# 8266_ultrasonic.net
KiCad netlist of a schematic drawn in EAGLE
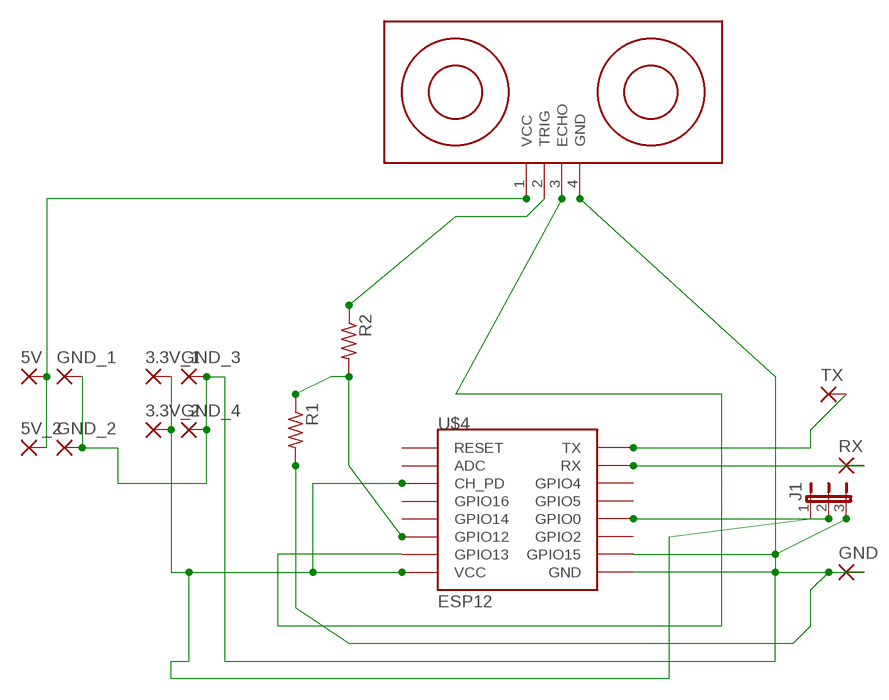
[diagram p0: schematic, sheet 1]

(export (version "E")
  (design (tool "Eeschema 10.0.6"))
  (components
    (comp (ref "3.3V_1")
      (value "2,15/1,0")
      (footprint "eagle-import:2,15_1,0")
      (libsource (lib "eagle-import") (part "2,15/1,0"))
    )
    (comp (ref "3.3V_2")
      (value "2,15/1,0")
      (footprint "eagle-import:2,15_1,0")
      (libsource (lib "eagle-import") (part "2,15/1,0"))
    )
    (comp (ref "5V")
      (value "2,15/1,0")
      (footprint "eagle-import:2,15_1,0")
      (libsource (lib "eagle-import") (part "2,15/1,0"))
    )
    (comp (ref "5V_2")
      (value "2,15/1,0")
      (footprint "eagle-import:2,15_1,0")
      (libsource (lib "eagle-import") (part "2,15/1,0"))
    )
    (comp (ref "GND")
      (value "2,15/1,0")
      (footprint "eagle-import:2,15_1,0")
      (libsource (lib "eagle-import") (part "2,15/1,0"))
    )
    (comp (ref "GND_1")
      (value "2,15/1,0")
      (footprint "eagle-import:2,15_1,0")
      (libsource (lib "eagle-import") (part "2,15/1,0"))
    )
    (comp (ref "GND_2")
      (value "2,15/1,0")
      (footprint "eagle-import:2,15_1,0")
      (libsource (lib "eagle-import") (part "2,15/1,0"))
    )
    (comp (ref "GND_3")
      (value "2,15/1,0")
      (footprint "eagle-import:2,15_1,0")
      (libsource (lib "eagle-import") (part "2,15/1,0"))
    )
    (comp (ref "GND_4")
      (value "2,15/1,0")
      (footprint "eagle-import:2,15_1,0")
      (libsource (lib "eagle-import") (part "2,15/1,0"))
    )
    (comp (ref "J1")
      (value "JP2E")
      (footprint "eagle-import:JP2")
      (libsource (lib "eagle-import") (part "JP2E"))
    )
    (comp (ref "R1")
      (value "R-US_0207/10")
      (footprint "eagle-import:0207_10")
      (libsource (lib "eagle-import") (part "R-US_0207/10"))
    )
    (comp (ref "R2")
      (value "R-US_0207/10")
      (footprint "eagle-import:0207_10")
      (libsource (lib "eagle-import") (part "R-US_0207/10"))
    )
    (comp (ref "RX")
      (value "2,15/1,0")
      (footprint "eagle-import:2,15_1,0")
      (libsource (lib "eagle-import") (part "2,15/1,0"))
    )
    (comp (ref "TX")
      (value "2,15/1,0")
      (footprint "eagle-import:2,15_1,0")
      (libsource (lib "eagle-import") (part "2,15/1,0"))
    )
    (comp (ref "U$3")
      (value "ULTRASONIC-HC-SR04#V")
      (footprint "eagle-import:ULTRASONIC-HC-SR04#V")
      (libsource (lib "eagle-import") (part "ULTRASONIC-HC-SR04#V"))
    )
    (comp (ref "U$4")
      (value "ESP12")
      (footprint "eagle-import:ESP12")
      (libsource (lib "eagle-import") (part "ESP12"))
    )
  )
  (nets
    (net (code "1") (name "Net-(3.3V_1-P)") (class "Default")
      (node (ref "3.3V_1") (pin "1") (pinfunction "P_1") (pintype "passive"))
      (node (ref "3.3V_2") (pin "1") (pinfunction "P_1") (pintype "passive"))
      (node (ref "J1") (pin "1") (pinfunction "1_1") (pintype "passive"))
      (node (ref "U$4") (pin "CH_PD") (pinfunction "CH_PD_CH_PD") (pintype "bidirectional"))
      (node (ref "U$4") (pin "VCC") (pinfunction "VCC_VCC") (pintype "bidirectional"))
    )
    (net (code "2") (name "Net-(5V-P)") (class "Default")
      (node (ref "5V") (pin "1") (pinfunction "P_1") (pintype "passive"))
      (node (ref "5V_2") (pin "1") (pinfunction "P_1") (pintype "passive"))
      (node (ref "U$3") (pin "1") (pinfunction "VCC_1") (pintype "power_in"))
    )
    (net (code "3") (name "Net-(GND-P)") (class "Default")
      (node (ref "GND") (pin "1") (pinfunction "P_1") (pintype "passive"))
      (node (ref "GND_1") (pin "1") (pinfunction "P_1") (pintype "passive"))
      (node (ref "GND_2") (pin "1") (pinfunction "P_1") (pintype "passive"))
      (node (ref "GND_3") (pin "1") (pinfunction "P_1") (pintype "passive"))
      (node (ref "GND_4") (pin "1") (pinfunction "P_1") (pintype "passive"))
      (node (ref "J1") (pin "3") (pinfunction "3_3") (pintype "passive"))
      (node (ref "R1") (pin "2") (pinfunction "2_2") (pintype "passive"))
      (node (ref "U$3") (pin "4") (pinfunction "GND_4") (pintype "power_in"))
      (node (ref "U$4") (pin "GND") (pinfunction "GND_GND") (pintype "bidirectional"))
      (node (ref "U$4") (pin "GPIO15") (pinfunction "GPIO15_GPIO15") (pintype "bidirectional"))
    )
    (net (code "4") (name "Net-(J1-Pad2)") (class "Default")
      (node (ref "J1") (pin "2") (pinfunction "2_2") (pintype "passive"))
      (node (ref "U$4") (pin "GPIO0") (pinfunction "GPIO0_GPIO0") (pintype "bidirectional"))
    )
    (net (code "5") (name "Net-(R1-Pad1)") (class "Default")
      (node (ref "R1") (pin "1") (pinfunction "1_1") (pintype "passive"))
      (node (ref "R2") (pin "2") (pinfunction "2_2") (pintype "passive"))
      (node (ref "U$4") (pin "GPIO12") (pinfunction "GPIO12_GPIO12") (pintype "bidirectional"))
    )
    (net (code "6") (name "Net-(RX-P)") (class "Default")
      (node (ref "RX") (pin "1") (pinfunction "P_1") (pintype "passive"))
      (node (ref "U$4") (pin "RX") (pinfunction "RX_RX") (pintype "bidirectional"))
    )
    (net (code "7") (name "Net-(TX-P)") (class "Default")
      (node (ref "TX") (pin "1") (pinfunction "P_1") (pintype "passive"))
      (node (ref "U$4") (pin "TX") (pinfunction "TX_TX") (pintype "bidirectional"))
    )
    (net (code "8") (name "Net-(U$3-ECHO)") (class "Default")
      (node (ref "U$3") (pin "3") (pinfunction "ECHO_3") (pintype "output"))
      (node (ref "U$4") (pin "GPIO13") (pinfunction "GPIO13_GPIO13") (pintype "bidirectional"))
    )
    (net (code "9") (name "Net-(U$3-TRIG)") (class "Default")
      (node (ref "R2") (pin "1") (pinfunction "1_1") (pintype "passive"))
      (node (ref "U$3") (pin "2") (pinfunction "TRIG_2") (pintype "input"))
    )
    (net (code "10") (name "unconnected-(U$4-PadADC)") (class "Default")
      (node (ref "U$4") (pin "ADC") (pinfunction "ADC_ADC") (pintype "bidirectional"))
    )
    (net (code "11") (name "unconnected-(U$4-PadGPIO2)") (class "Default")
      (node (ref "U$4") (pin "GPIO2") (pinfunction "GPIO2_GPIO2") (pintype "bidirectional"))
    )
    (net (code "12") (name "unconnected-(U$4-PadGPIO4)") (class "Default")
      (node (ref "U$4") (pin "GPIO4") (pinfunction "GPIO4_GPIO4") (pintype "bidirectional"))
    )
    (net (code "13") (name "unconnected-(U$4-PadGPIO5)") (class "Default")
      (node (ref "U$4") (pin "GPIO5") (pinfunction "GPIO5_GPIO5") (pintype "bidirectional"))
    )
    (net (code "14") (name "unconnected-(U$4-PadGPIO14)") (class "Default")
      (node (ref "U$4") (pin "GPIO14") (pinfunction "GPIO14_GPIO14") (pintype "bidirectional"))
    )
    (net (code "15") (name "unconnected-(U$4-PadGPIO16)") (class "Default")
      (node (ref "U$4") (pin "GPIO16") (pinfunction "GPIO16_GPIO16") (pintype "bidirectional"))
    )
    (net (code "16") (name "unconnected-(U$4-PadRESET)") (class "Default")
      (node (ref "U$4") (pin "RESET") (pinfunction "RESET_RESET") (pintype "bidirectional"))
    )
  )
)
